# SCH_d_00_ex_03.net
KiCad netlist of a schematic drawn in EasyEDA
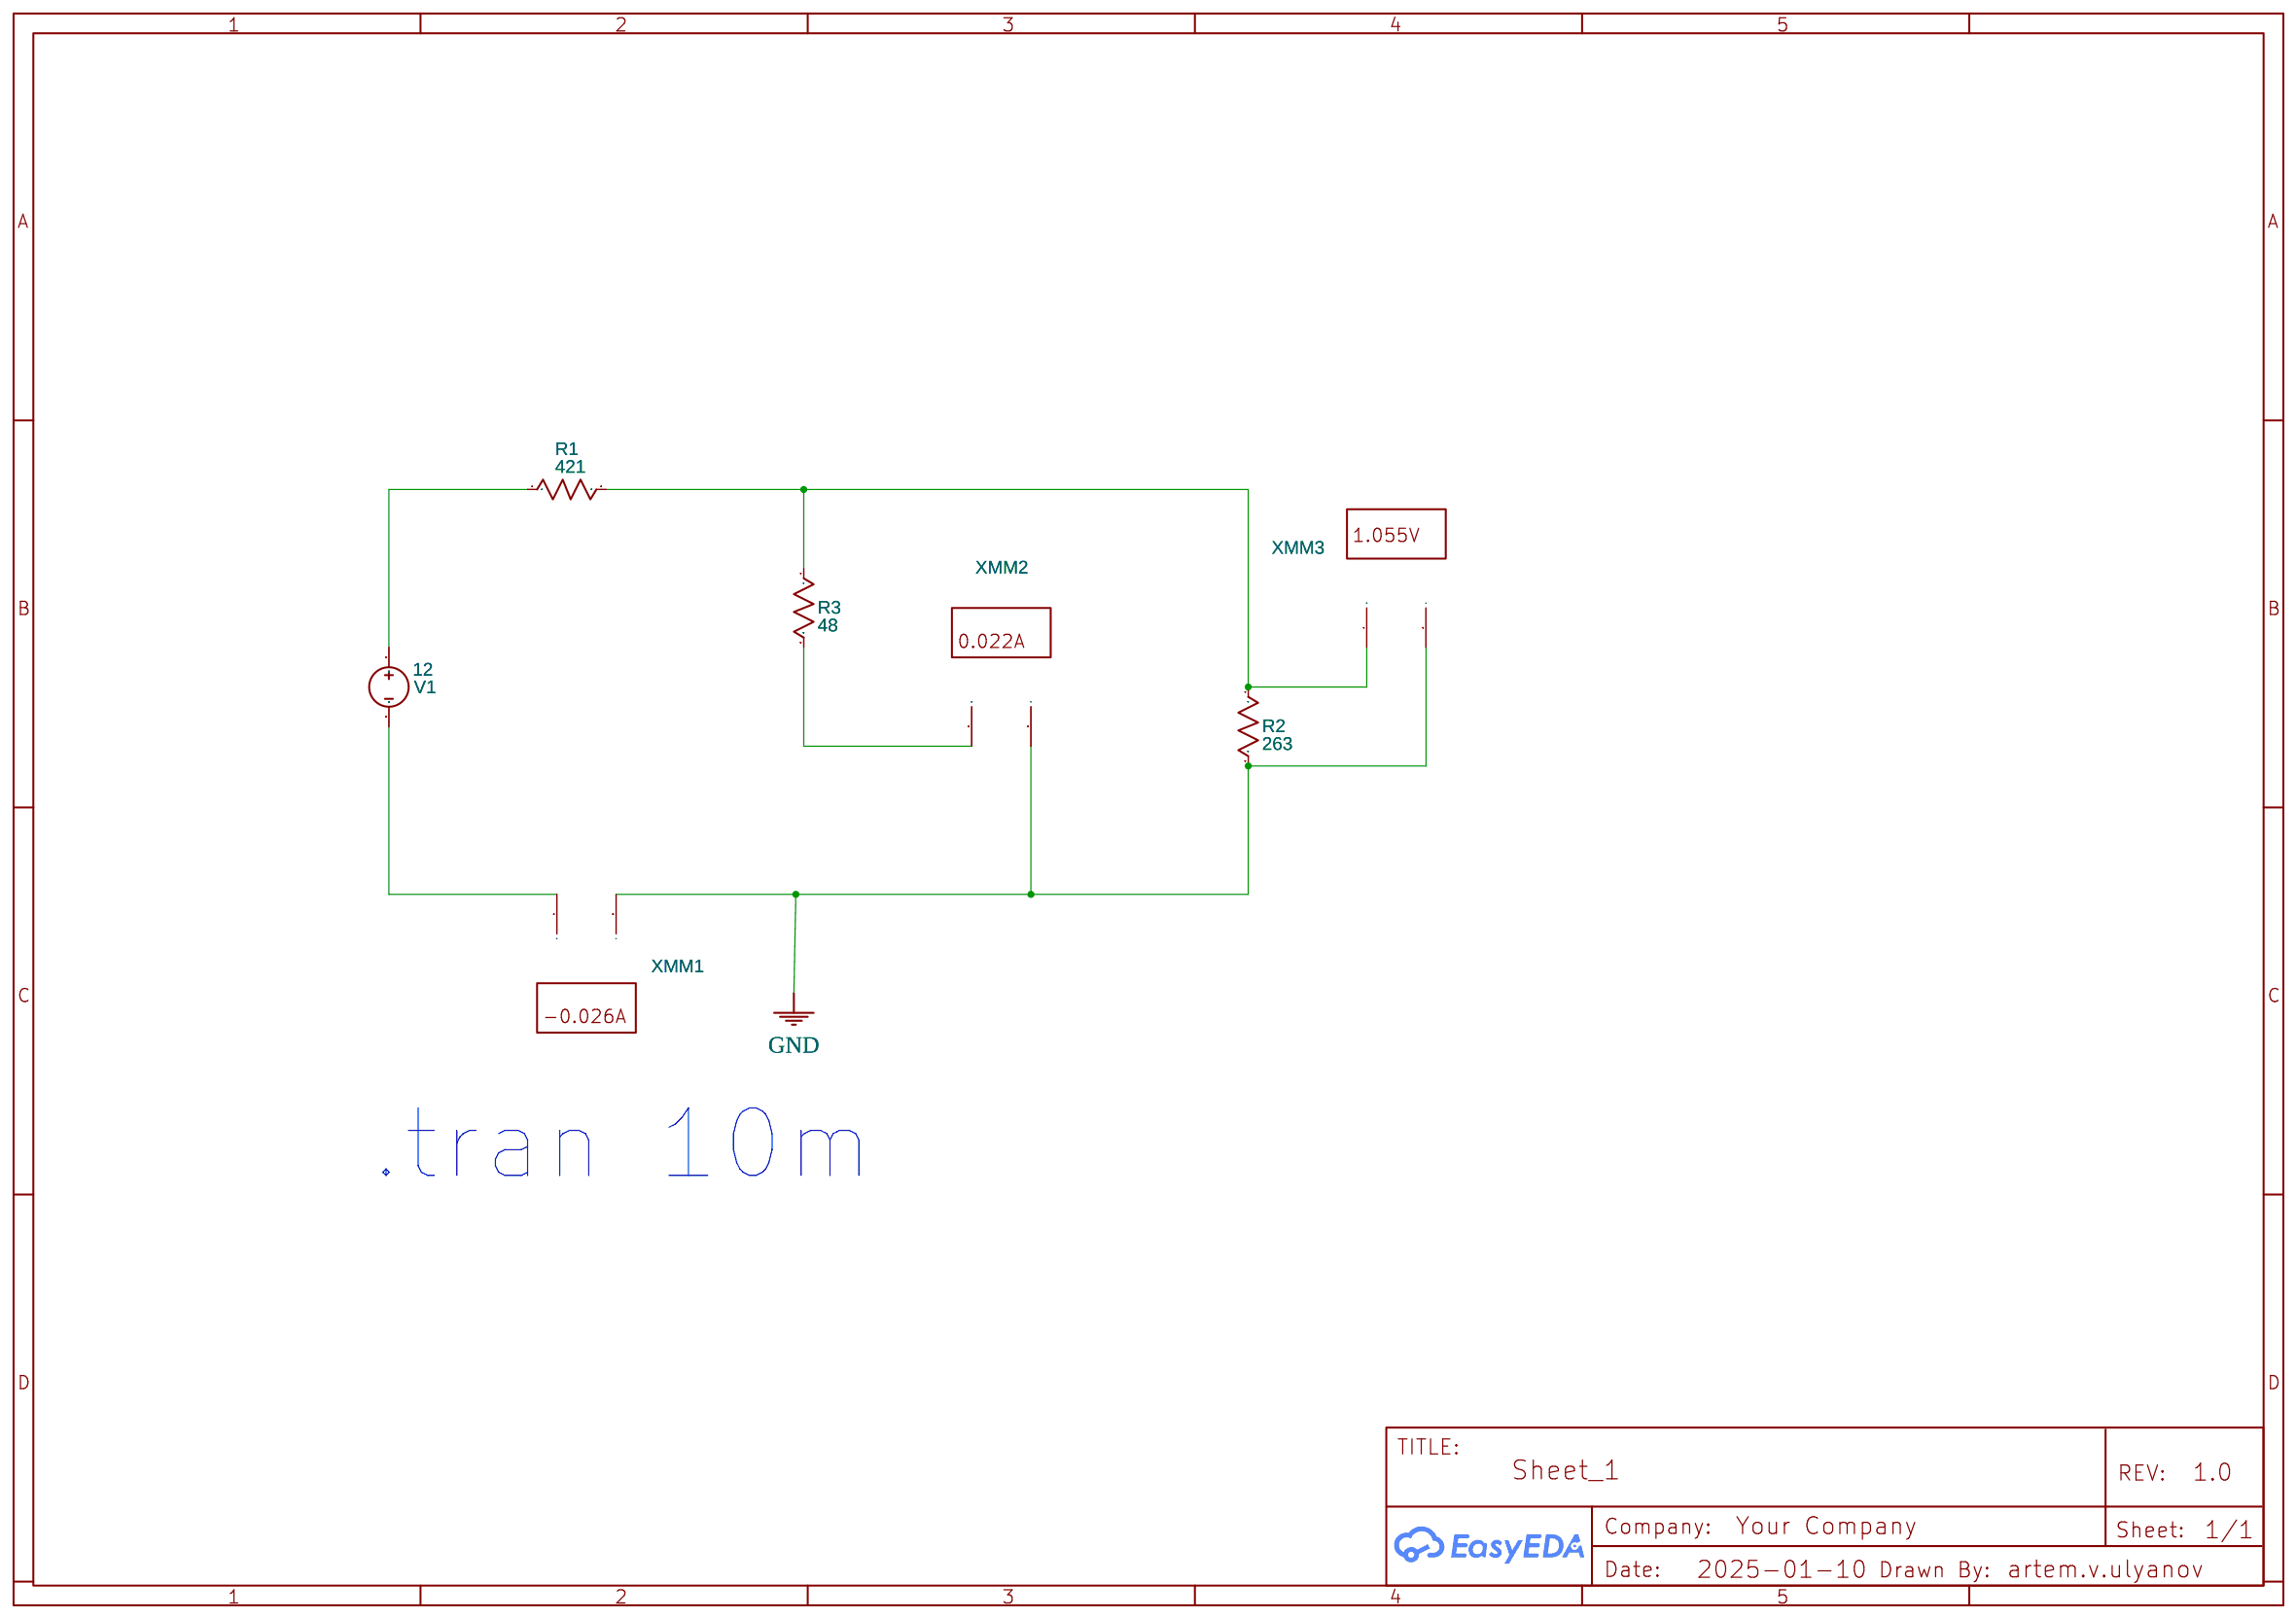
[diagram p0: schematic sheet]

(export (version "E")
  (design (tool "Eeschema 10.0.6"))
  (components
    (comp (ref "R1") (value "421") (libsource (lib "") (part "Resistor_US_1")))
    (comp (ref "R2") (value "263") (libsource (lib "") (part "Resistor_US")))
    (comp (ref "R3") (value "48") (libsource (lib "") (part "Resistor_US")))
    (comp (ref "V1") (value "12") (libsource (lib "") (part "VDC")))
    (comp (ref "XMM1") (value "Multimeter") (libsource (lib "") (part "MULTIMETER")))
    (comp (ref "XMM2") (value "Multimeter") (libsource (lib "") (part "MULTIMETER_2")))
    (comp (ref "XMM3") (value "Multimeter") (libsource (lib "") (part "MULTIMETER_1")))
  )
  (nets
    (net (code "1") (name "GND") (class "Default")
      (node (ref "R2") (pin "2") (pinfunction "2_2") (pintype "unspecified"))
      (node (ref "XMM1") (pin "2") (pinfunction "I_2") (pintype "unspecified"))
      (node (ref "XMM2") (pin "2") (pinfunction "I_2") (pintype "unspecified"))
      (node (ref "XMM3") (pin "2") (pinfunction "I_2") (pintype "unspecified"))
    )
    (net (code "2") (name "Net-(R1-Pad1)") (class "Default")
      (node (ref "R1") (pin "1") (pinfunction "1_1") (pintype "unspecified"))
      (node (ref "V1") (pin "1") (pinfunction "1_1") (pintype "unspecified"))
    )
    (net (code "3") (name "Net-(XMM1-+)") (class "Default")
      (node (ref "V1") (pin "2") (pinfunction "2_2") (pintype "unspecified"))
      (node (ref "XMM1") (pin "1") (pinfunction "+_1") (pintype "unspecified"))
    )
    (net (code "4") (name "Net-(XMM2-+)") (class "Default")
      (node (ref "R3") (pin "2") (pinfunction "2_2") (pintype "unspecified"))
      (node (ref "XMM2") (pin "1") (pinfunction "+_1") (pintype "unspecified"))
    )
    (net (code "5") (name "Net-(XMM3-+)") (class "Default")
      (node (ref "R1") (pin "2") (pinfunction "2_2") (pintype "unspecified"))
      (node (ref "R2") (pin "1") (pinfunction "1_1") (pintype "unspecified"))
      (node (ref "R3") (pin "1") (pinfunction "1_1") (pintype "unspecified"))
      (node (ref "XMM3") (pin "1") (pinfunction "+_1") (pintype "unspecified"))
    )
  )
)
